# plugV15-smd-5x5cm-small-pinout.net
KiCad netlist of a schematic drawn in EAGLE
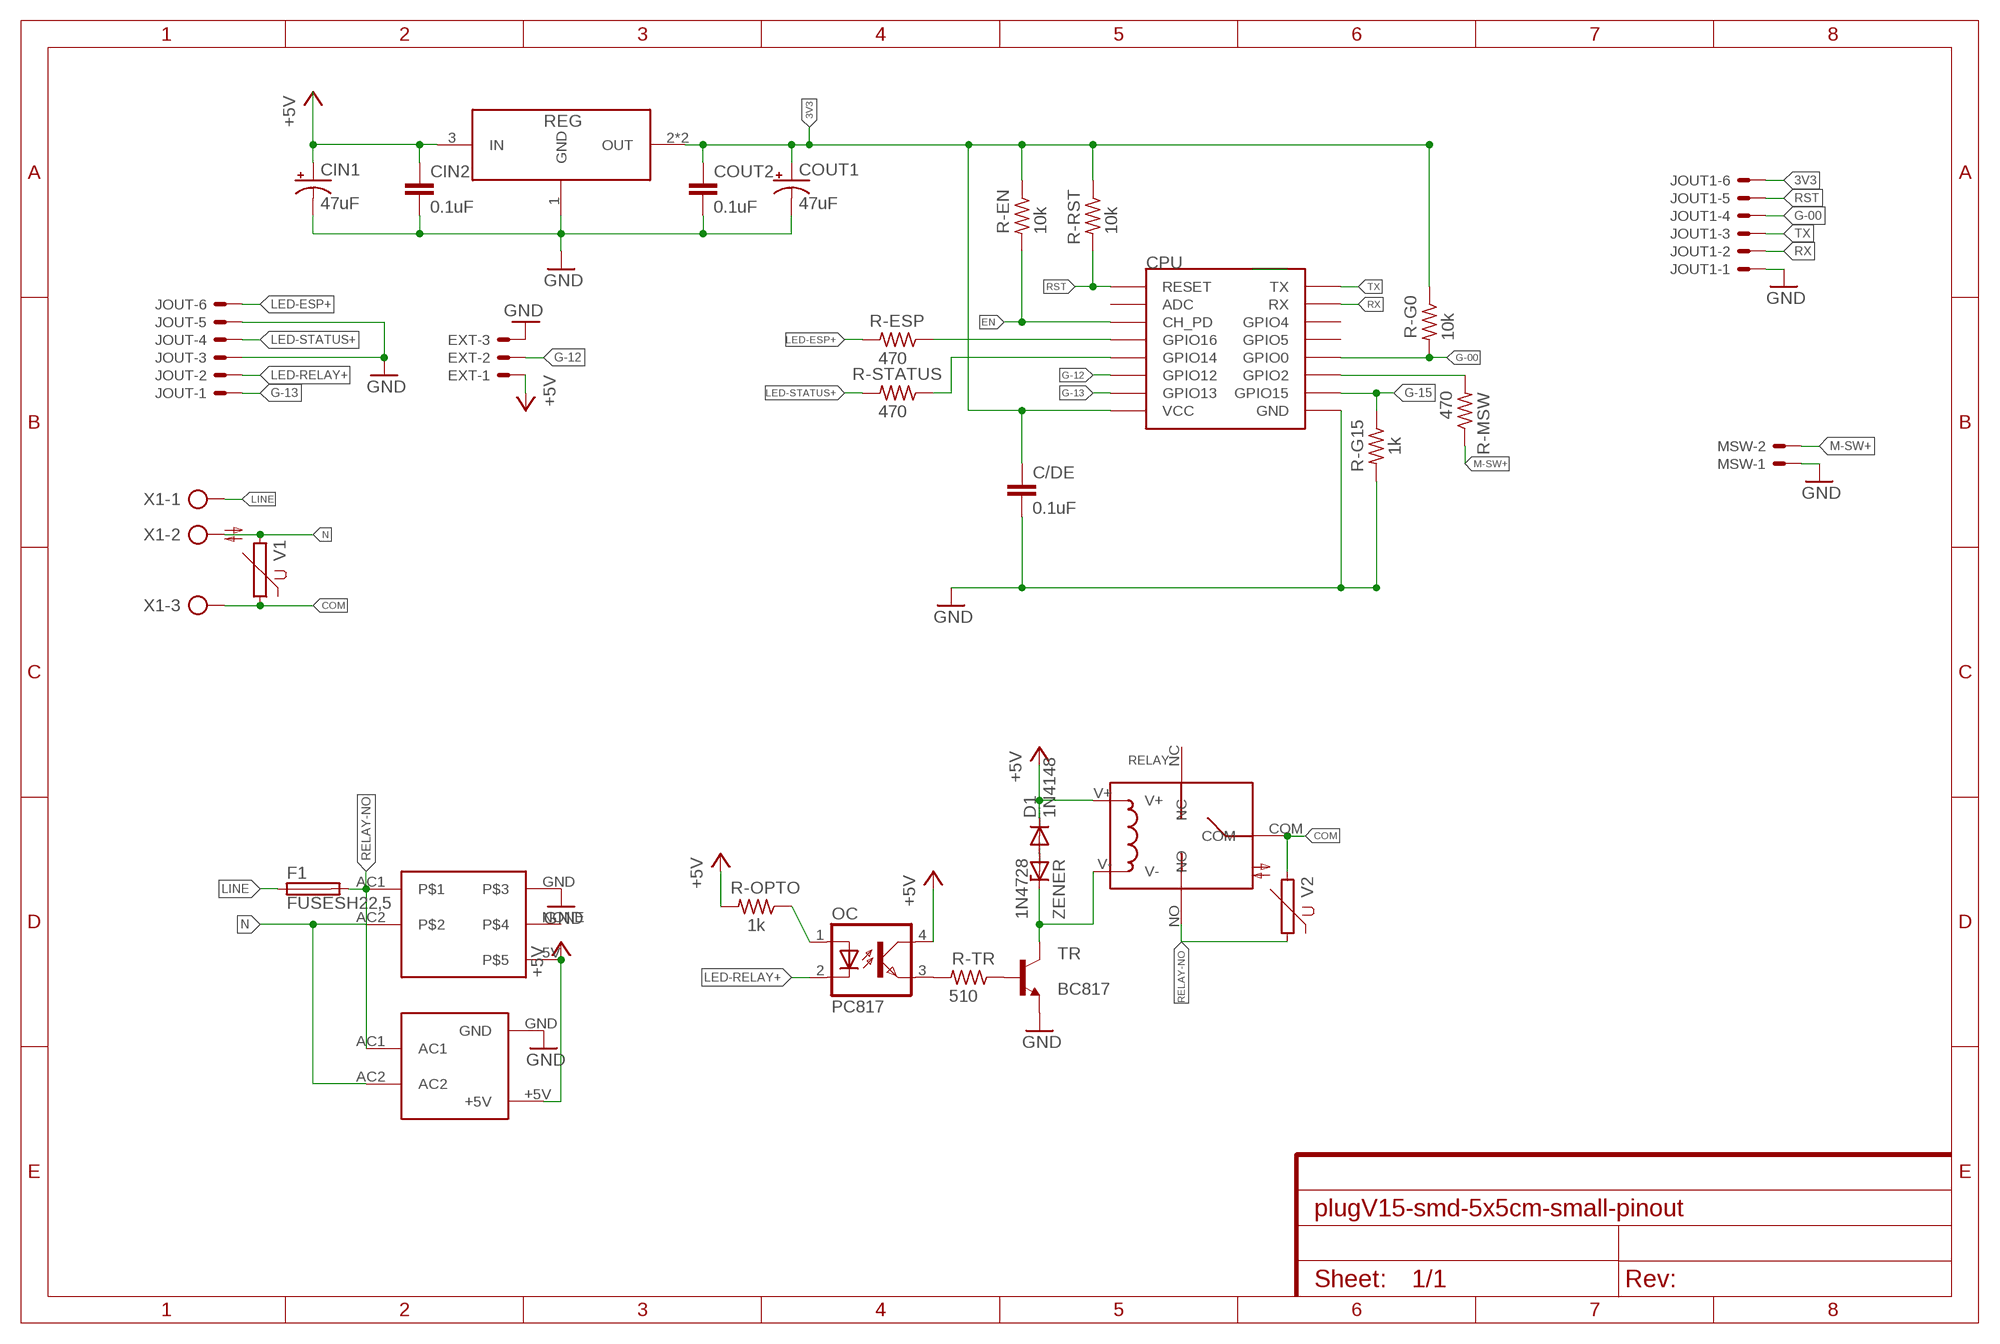
[diagram p0: schematic, sheet 1]

(export (version "E")
  (design (tool "Eeschema 10.0.6"))
  (components
    (comp (ref "C/DE")
      (value "0.1uF")
      (footprint "eagle-import:C0805")
      (libsource (lib "eagle-import") (part "C-EUC0805"))
    )
    (comp (ref "CIN1")
      (value "47uF")
      (footprint "eagle-import:E2,5-5")
      (libsource (lib "eagle-import") (part "CPOL-USE2.5-5"))
    )
    (comp (ref "CIN2")
      (value "0.1uF")
      (footprint "eagle-import:C0805")
      (libsource (lib "eagle-import") (part "C-EUC0805"))
    )
    (comp (ref "COUT1")
      (value "47uF")
      (footprint "eagle-import:E2,5-5")
      (libsource (lib "eagle-import") (part "CPOL-USE2.5-5"))
    )
    (comp (ref "COUT2")
      (value "0.1uF")
      (footprint "eagle-import:C0805")
      (libsource (lib "eagle-import") (part "C-EUC0805"))
    )
    (comp (ref "CPU")
      (value "ESP12SMD")
      (footprint "eagle-import:ESP12-SMD")
      (libsource (lib "eagle-import") (part "ESP12SMD"))
    )
    (comp (ref "D1")
      (value "1N4148")
      (footprint "eagle-import:DO35-7")
      (libsource (lib "eagle-import") (part "1N4148DO35-7"))
    )
    (comp (ref "EXT")
      (value "53048-03")
      (footprint "eagle-import:53048-03")
      (fields (field (name "MF") "WALDOM/MOLEX") (field (name "MPN") "53048-0310"))
      (libsource (lib "eagle-import") (part "53?-03048"))
    )
    (comp (ref "F1")
      (value "FUSESH22,5")
      (footprint "eagle-import:SH22,5")
      (libsource (lib "eagle-import") (part "FUSESH22,5"))
    )
    (comp (ref "HLK")
      (value "HLK-PM01")
      (footprint "eagle-import:HLK-PM01")
      (libsource (lib "eagle-import") (part "HLK-PM01"))
    )
    (comp (ref "JOUT")
      (value "53048-06")
      (footprint "eagle-import:53048-06")
      (fields (field (name "MF") "WALDOM/MOLEX") (field (name "MPN") "53048-0610"))
      (libsource (lib "eagle-import") (part "53?-06048"))
    )
    (comp (ref "JOUT1")
      (value "53048-06")
      (footprint "eagle-import:53048-06")
      (fields (field (name "MF") "WALDOM/MOLEX") (field (name "MPN") "53048-0610"))
      (libsource (lib "eagle-import") (part "53?-06048"))
    )
    (comp (ref "MSW")
      (value "53048-02")
      (footprint "eagle-import:53048-02")
      (fields (field (name "MF") "MOLEX") (field (name "MPN") "53048-0210"))
      (libsource (lib "eagle-import") (part "53?-02048"))
    )
    (comp (ref "OC")
      (value "PC817")
      (footprint "eagle-import:DIL04")
      (fields (field (name "MPN") "PC817X4J000F"))
      (libsource (lib "eagle-import") (part "PC817"))
    )
    (comp (ref "R-EN")
      (value "10k")
      (footprint "eagle-import:M0805")
      (libsource (lib "eagle-import") (part "R-US_M0805"))
    )
    (comp (ref "R-ESP")
      (value "470")
      (footprint "eagle-import:M0805")
      (libsource (lib "eagle-import") (part "R-US_M0805"))
    )
    (comp (ref "R-G0")
      (value "10k")
      (footprint "eagle-import:M0805")
      (libsource (lib "eagle-import") (part "R-US_M0805"))
    )
    (comp (ref "R-G15")
      (value "1k")
      (footprint "eagle-import:M0805")
      (libsource (lib "eagle-import") (part "R-US_M0805"))
    )
    (comp (ref "R-MSW")
      (value "470")
      (footprint "eagle-import:M0805")
      (libsource (lib "eagle-import") (part "R-US_M0805"))
    )
    (comp (ref "R-OPTO")
      (value "1k")
      (footprint "eagle-import:M0805")
      (libsource (lib "eagle-import") (part "R-US_M0805"))
    )
    (comp (ref "R-RST")
      (value "10k")
      (footprint "eagle-import:M0805")
      (libsource (lib "eagle-import") (part "R-US_M0805"))
    )
    (comp (ref "R-STATUS")
      (value "470")
      (footprint "eagle-import:M0805")
      (libsource (lib "eagle-import") (part "R-US_M0805"))
    )
    (comp (ref "R-TR")
      (value "510")
      (footprint "eagle-import:M0805")
      (libsource (lib "eagle-import") (part "R-US_M0805"))
    )
    (comp (ref "REG")
      (value "AMS1117-3.3")
      (footprint "eagle-import:SOT-223")
      (libsource (lib "eagle-import") (part "AMS1117-3.3"))
    )
    (comp (ref "RELAY")
      (value "RELAY-SONGLE")
      (footprint "eagle-import:RELAY-SONGLE")
      (libsource (lib "eagle-import") (part "RELAY-SONGLE"))
    )
    (comp (ref "TR")
      (value "BC817")
      (footprint "eagle-import:SOT23-BEC")
      (libsource (lib "eagle-import") (part "BC817SMD-16"))
    )
    (comp (ref "U$4")
      (value "POWERSUPPLY-5V-700MA")
      (footprint "eagle-import:POWERSUPPLY-5V-700MA")
      (libsource (lib "eagle-import") (part "POWERSUPPLY-5V-700MA"))
    )
    (comp (ref "V1")
      (value "S14K11")
      (footprint "eagle-import:S14K11")
      (libsource (lib "eagle-import") (part "S14K11"))
    )
    (comp (ref "V2")
      (value "S14K11")
      (footprint "eagle-import:S14K11")
      (libsource (lib "eagle-import") (part "S14K11"))
    )
    (comp (ref "X1")
      (value "AK300/3")
      (footprint "eagle-import:AK300_3")
      (libsource (lib "eagle-import") (part "AK300/3"))
    )
    (comp (ref "ZENER")
      (value "1N4728")
      (footprint "eagle-import:DO41Z10")
      (libsource (lib "eagle-import") (part "1N4728"))
    )
  )
  (nets
    (net (code "1") (name "+5V") (class "Default")
      (node (ref "CIN1") (pin "+") (pinfunction "+_+") (pintype "passive"))
      (node (ref "CIN2") (pin "1") (pinfunction "1_1") (pintype "passive"))
      (node (ref "D1") (pin "C") (pinfunction "C_C") (pintype "passive"))
      (node (ref "EXT") (pin "1") (pinfunction "S_1") (pintype "passive"))
      (node (ref "HLK") (pin "+5V") (pinfunction "+5V_+5V") (pintype "bidirectional"))
      (node (ref "OC") (pin "4") (pinfunction "COL_4") (pintype "passive"))
      (node (ref "R-OPTO") (pin "2") (pinfunction "2_2") (pintype "passive"))
      (node (ref "REG") (pin "3") (pinfunction "IN_3") (pintype "input"))
      (node (ref "RELAY") (pin "V+") (pinfunction "V+_V+") (pintype "bidirectional"))
      (node (ref "U$4") (pin "5V") (pinfunction "P$5_5V") (pintype "bidirectional"))
    )
    (net (code "2") (name "3V3") (class "Default")
      (node (ref "C/DE") (pin "1") (pinfunction "1_1") (pintype "passive"))
      (node (ref "COUT1") (pin "+") (pinfunction "+_+") (pintype "passive"))
      (node (ref "COUT2") (pin "1") (pinfunction "1_1") (pintype "passive"))
      (node (ref "CPU") (pin "VCC") (pinfunction "VCC_VCC") (pintype "bidirectional"))
      (node (ref "JOUT1") (pin "6") (pinfunction "S_6") (pintype "passive"))
      (node (ref "R-EN") (pin "1") (pinfunction "1_1") (pintype "passive"))
      (node (ref "R-G0") (pin "1") (pinfunction "1_1") (pintype "passive"))
      (node (ref "R-RST") (pin "1") (pinfunction "1_1") (pintype "passive"))
      (node (ref "REG") (pin "2") (pinfunction "OUT_2") (pintype "output"))
      (node (ref "REG") (pin "4") (pinfunction "OUT_4") (pintype "output"))
    )
    (net (code "3") (name "COM") (class "Default")
      (node (ref "RELAY") (pin "COM") (pinfunction "COM_COM") (pintype "bidirectional"))
      (node (ref "V1") (pin "1") (pinfunction "1_1") (pintype "passive"))
      (node (ref "V2") (pin "2") (pinfunction "2_2") (pintype "passive"))
      (node (ref "X1") (pin "3") (pinfunction "KL_3") (pintype "passive"))
    )
    (net (code "4") (name "EN") (class "Default")
      (node (ref "CPU") (pin "CH_PD") (pinfunction "CH_PD_CH_PD") (pintype "bidirectional"))
      (node (ref "R-EN") (pin "2") (pinfunction "2_2") (pintype "passive"))
    )
    (net (code "5") (name "G-00") (class "Default")
      (node (ref "CPU") (pin "GPIO0") (pinfunction "GPIO0_GPIO0") (pintype "bidirectional"))
      (node (ref "JOUT1") (pin "4") (pinfunction "S_4") (pintype "passive"))
      (node (ref "R-G0") (pin "2") (pinfunction "2_2") (pintype "passive"))
    )
    (net (code "6") (name "G-12") (class "Default")
      (node (ref "CPU") (pin "GPIO12") (pinfunction "GPIO12_GPIO12") (pintype "bidirectional"))
      (node (ref "EXT") (pin "2") (pinfunction "S_2") (pintype "passive"))
    )
    (net (code "7") (name "G-13") (class "Default")
      (node (ref "CPU") (pin "GPIO13") (pinfunction "GPIO13_GPIO13") (pintype "bidirectional"))
      (node (ref "JOUT") (pin "1") (pinfunction "S_1") (pintype "passive"))
    )
    (net (code "8") (name "G-15") (class "Default")
      (node (ref "CPU") (pin "GPIO15") (pinfunction "GPIO15_GPIO15") (pintype "bidirectional"))
      (node (ref "R-G15") (pin "1") (pinfunction "1_1") (pintype "passive"))
    )
    (net (code "9") (name "GND") (class "Default")
      (node (ref "C/DE") (pin "2") (pinfunction "2_2") (pintype "passive"))
      (node (ref "CIN1") (pin "-") (pinfunction "-_-") (pintype "passive"))
      (node (ref "CIN2") (pin "2") (pinfunction "2_2") (pintype "passive"))
      (node (ref "COUT1") (pin "-") (pinfunction "-_-") (pintype "passive"))
      (node (ref "COUT2") (pin "2") (pinfunction "2_2") (pintype "passive"))
      (node (ref "CPU") (pin "GND") (pinfunction "GND_GND") (pintype "bidirectional"))
      (node (ref "EXT") (pin "3") (pinfunction "S_3") (pintype "passive"))
      (node (ref "HLK") (pin "GND") (pinfunction "GND_GND") (pintype "bidirectional"))
      (node (ref "JOUT") (pin "3") (pinfunction "S_3") (pintype "passive"))
      (node (ref "JOUT") (pin "5") (pinfunction "S_5") (pintype "passive"))
      (node (ref "JOUT1") (pin "1") (pinfunction "S_1") (pintype "passive"))
      (node (ref "MSW") (pin "1") (pinfunction "S_1") (pintype "passive"))
      (node (ref "R-G15") (pin "2") (pinfunction "2_2") (pintype "passive"))
      (node (ref "REG") (pin "1") (pinfunction "GND_1") (pintype "passive"))
      (node (ref "TR") (pin "E") (pinfunction "E_E") (pintype "passive"))
      (node (ref "U$4") (pin "GND") (pinfunction "P$3_GND") (pintype "bidirectional"))
    )
    (net (code "10") (name "LED-ESP+") (class "Default")
      (node (ref "JOUT") (pin "6") (pinfunction "S_6") (pintype "passive"))
      (node (ref "R-ESP") (pin "2") (pinfunction "2_2") (pintype "passive"))
    )
    (net (code "11") (name "LED-RELAY+") (class "Default")
      (node (ref "JOUT") (pin "2") (pinfunction "S_2") (pintype "passive"))
      (node (ref "OC") (pin "2") (pinfunction "C_2") (pintype "passive"))
    )
    (net (code "12") (name "LED-STATUS+") (class "Default")
      (node (ref "JOUT") (pin "4") (pinfunction "S_4") (pintype "passive"))
      (node (ref "R-STATUS") (pin "2") (pinfunction "2_2") (pintype "passive"))
    )
    (net (code "13") (name "LINE") (class "Default")
      (node (ref "F1") (pin "1") (pinfunction "1_1") (pintype "passive"))
      (node (ref "X1") (pin "1") (pinfunction "KL_1") (pintype "passive"))
    )
    (net (code "14") (name "M-SW+") (class "Default")
      (node (ref "MSW") (pin "2") (pinfunction "S_2") (pintype "passive"))
      (node (ref "R-MSW") (pin "1") (pinfunction "1_1") (pintype "passive"))
    )
    (net (code "15") (name "N") (class "Default")
      (node (ref "HLK") (pin "AC2") (pinfunction "AC2_AC2") (pintype "bidirectional"))
      (node (ref "U$4") (pin "AC2") (pinfunction "P$2_AC2") (pintype "bidirectional"))
      (node (ref "V1") (pin "2") (pinfunction "2_2") (pintype "passive"))
      (node (ref "X1") (pin "2") (pinfunction "KL_2") (pintype "passive"))
    )
    (net (code "16") (name "Net-(CPU-PadGPIO2)") (class "Default")
      (node (ref "CPU") (pin "GPIO2") (pinfunction "GPIO2_GPIO2") (pintype "bidirectional"))
      (node (ref "R-MSW") (pin "2") (pinfunction "2_2") (pintype "passive"))
    )
    (net (code "17") (name "Net-(CPU-PadGPIO14)") (class "Default")
      (node (ref "CPU") (pin "GPIO14") (pinfunction "GPIO14_GPIO14") (pintype "bidirectional"))
      (node (ref "R-STATUS") (pin "1") (pinfunction "1_1") (pintype "passive"))
    )
    (net (code "18") (name "Net-(CPU-PadGPIO16)") (class "Default")
      (node (ref "CPU") (pin "GPIO16") (pinfunction "GPIO16_GPIO16") (pintype "bidirectional"))
      (node (ref "R-ESP") (pin "1") (pinfunction "1_1") (pintype "passive"))
    )
    (net (code "19") (name "Net-(D1-PadA)") (class "Default")
      (node (ref "D1") (pin "A") (pinfunction "A_A") (pintype "passive"))
      (node (ref "ZENER") (pin "A") (pinfunction "A_A") (pintype "passive"))
    )
    (net (code "20") (name "Net-(OC-A)") (class "Default")
      (node (ref "OC") (pin "1") (pinfunction "A_1") (pintype "passive"))
      (node (ref "R-OPTO") (pin "1") (pinfunction "1_1") (pintype "passive"))
    )
    (net (code "21") (name "Net-(OC-EMIT)") (class "Default")
      (node (ref "OC") (pin "3") (pinfunction "EMIT_3") (pintype "passive"))
      (node (ref "R-TR") (pin "2") (pinfunction "2_2") (pintype "passive"))
    )
    (net (code "22") (name "Net-(R-TR-Pad1)") (class "Default")
      (node (ref "R-TR") (pin "1") (pinfunction "1_1") (pintype "passive"))
      (node (ref "TR") (pin "B") (pinfunction "B_B") (pintype "passive"))
    )
    (net (code "23") (name "Net-(RELAY-PadV-)") (class "Default")
      (node (ref "RELAY") (pin "V-") (pinfunction "V-_V-") (pintype "bidirectional"))
      (node (ref "TR") (pin "C") (pinfunction "C_C") (pintype "passive"))
      (node (ref "ZENER") (pin "C") (pinfunction "C_C") (pintype "passive"))
    )
    (net (code "24") (name "RELAY-NO") (class "Default")
      (node (ref "F1") (pin "2") (pinfunction "2_2") (pintype "passive"))
      (node (ref "HLK") (pin "AC1") (pinfunction "AC1_AC1") (pintype "bidirectional"))
      (node (ref "RELAY") (pin "NO") (pinfunction "NO_NO") (pintype "bidirectional"))
      (node (ref "U$4") (pin "AC1") (pinfunction "P$1_AC1") (pintype "bidirectional"))
      (node (ref "V2") (pin "1") (pinfunction "1_1") (pintype "passive"))
    )
    (net (code "25") (name "RST") (class "Default")
      (node (ref "CPU") (pin "RESET") (pinfunction "RESET_RESET") (pintype "bidirectional"))
      (node (ref "JOUT1") (pin "5") (pinfunction "S_5") (pintype "passive"))
      (node (ref "R-RST") (pin "2") (pinfunction "2_2") (pintype "passive"))
    )
    (net (code "26") (name "RX") (class "Default")
      (node (ref "CPU") (pin "RXD0") (pinfunction "RX_RXD0") (pintype "bidirectional"))
      (node (ref "JOUT1") (pin "2") (pinfunction "S_2") (pintype "passive"))
    )
    (net (code "27") (name "TX") (class "Default")
      (node (ref "CPU") (pin "TXD0") (pinfunction "TX_TXD0") (pintype "bidirectional"))
      (node (ref "JOUT1") (pin "3") (pinfunction "S_3") (pintype "passive"))
    )
    (net (code "28") (name "unconnected-(CPU-PadADC)") (class "Default")
      (node (ref "CPU") (pin "ADC") (pinfunction "ADC_ADC") (pintype "bidirectional"))
    )
    (net (code "29") (name "unconnected-(CPU-PadGPIO4)") (class "Default")
      (node (ref "CPU") (pin "GPIO4") (pinfunction "GPIO4_GPIO4") (pintype "bidirectional"))
    )
    (net (code "30") (name "unconnected-(CPU-PadGPIO5)") (class "Default")
      (node (ref "CPU") (pin "GPIO5") (pinfunction "GPIO5_GPIO5") (pintype "bidirectional"))
    )
    (net (code "31") (name "unconnected-(RELAY-PadNC)") (class "Default")
      (node (ref "RELAY") (pin "NC") (pinfunction "NC_NC") (pintype "bidirectional"))
    )
    (net (code "32") (name "unconnected-(U$4-P$4-PadNONE)") (class "Default")
      (node (ref "U$4") (pin "NONE") (pinfunction "P$4_NONE") (pintype "bidirectional"))
    )
  )
)
